# MCU.net
KiCad netlist of a schematic drawn in Altium Designer
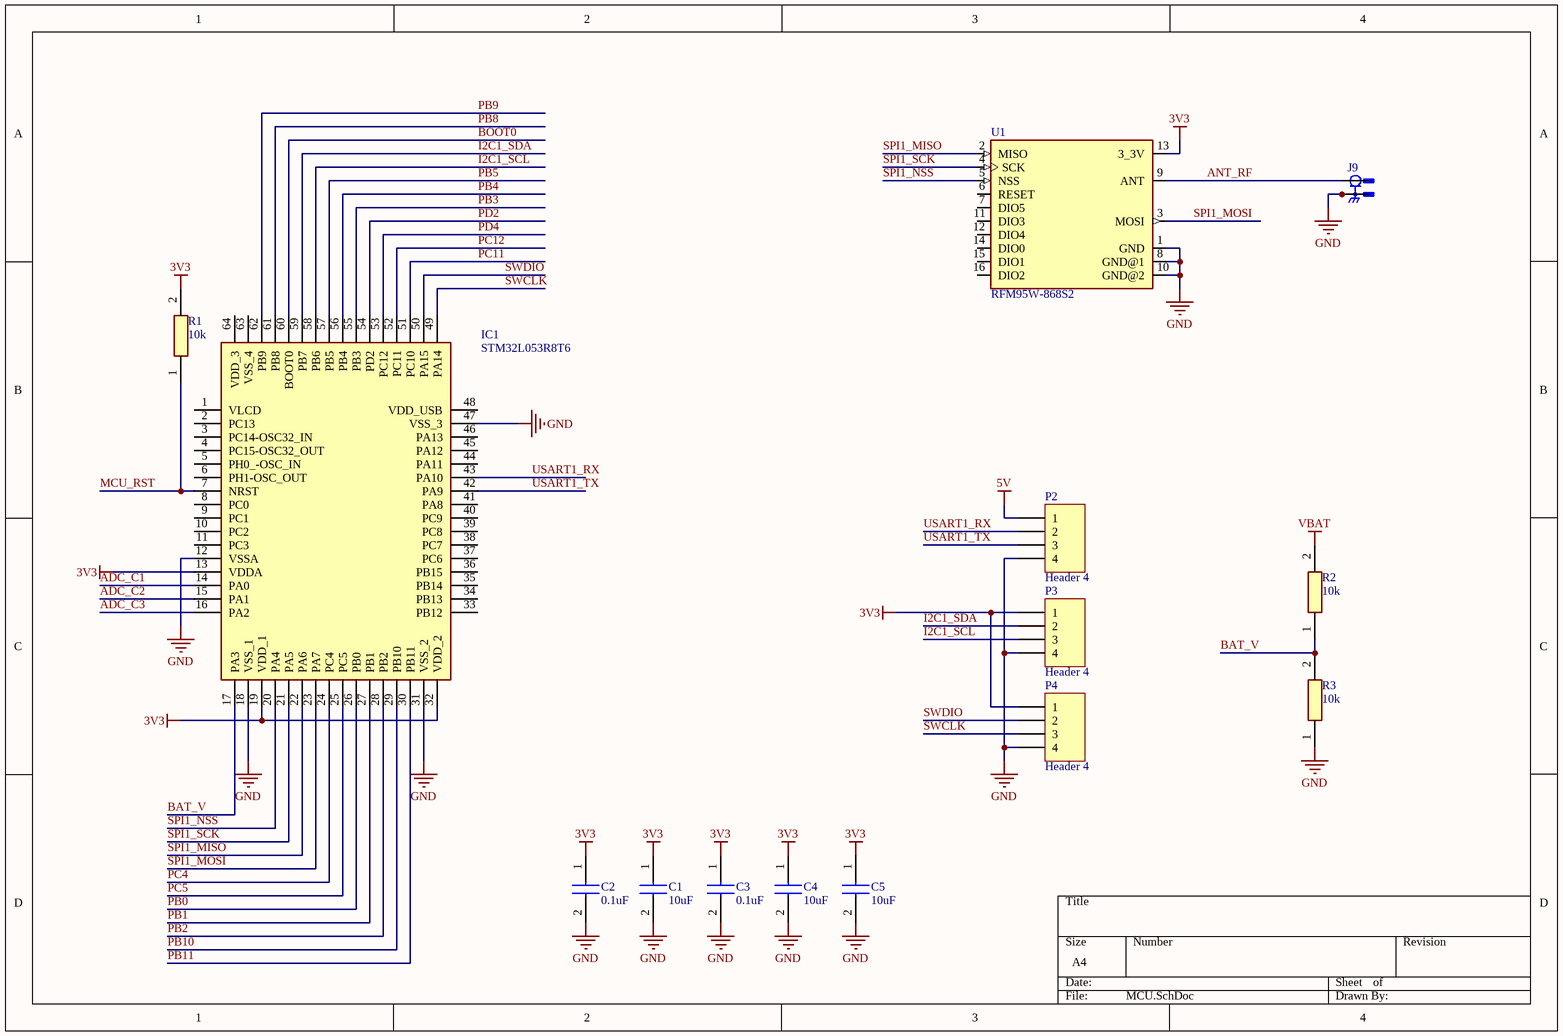
[diagram p0: MCU.SchDoc]

(export (version "E")
  (design (tool "Eeschema 10.0.6"))
  (components
    (comp (ref "C1")
      (value "10uF")
      (footprint "SamacSys:CAPC2012X94N")
      (description "Capacitor")
      (fields
        (field (name "MANUFACTURER_PART_NUMBER") "08055A130JAT2A")
        (field (name "MOUSER PART NUMBER") "581-08055A130JAT2A")
      )
      (libsource (lib "SamacSys") (part "08055A130JAT2A"))
    )
    (comp (ref "C2")
      (value "0.1uF")
      (footprint "SamacSys:CAPC2012X94N")
      (description "Capacitor")
      (fields
        (field (name "MANUFACTURER_PART_NUMBER") "08055A130JAT2A")
        (field (name "MOUSER PART NUMBER") "581-08055A130JAT2A")
      )
      (libsource (lib "SamacSys") (part "08055A130JAT2A"))
    )
    (comp (ref "C3")
      (value "0.1uF")
      (footprint "SamacSys:CAPC2012X94N")
      (description "Capacitor")
      (fields
        (field (name "MANUFACTURER_PART_NUMBER") "08055A130JAT2A")
        (field (name "MOUSER PART NUMBER") "581-08055A130JAT2A")
      )
      (libsource (lib "SamacSys") (part "08055A130JAT2A"))
    )
    (comp (ref "C4")
      (value "10uF")
      (footprint "SamacSys:CAPC2012X94N")
      (description "Capacitor")
      (fields
        (field (name "MANUFACTURER_PART_NUMBER") "08055A130JAT2A")
        (field (name "MOUSER PART NUMBER") "581-08055A130JAT2A")
      )
      (libsource (lib "SamacSys") (part "08055A130JAT2A"))
    )
    (comp (ref "C5")
      (value "10uF")
      (footprint "SamacSys:CAPC2012X94N")
      (description "Capacitor")
      (fields
        (field (name "MANUFACTURER_PART_NUMBER") "08055A130JAT2A")
        (field (name "MOUSER PART NUMBER") "581-08055A130JAT2A")
      )
      (libsource (lib "SamacSys") (part "08055A130JAT2A"))
    )
    (comp (ref "IC1")
      (value "STM32L053R8T6")
      (footprint "SamacSys:QFP50P1200X1200X160-64N")
      (description "Integrated Circuit")
      (fields (field (name "MOUSER PART NUMBER") "511-STM32L053R8T6"))
      (libsource (lib "*") (part "STM32L053R8T6"))
    )
    (comp (ref "J9")
      (value "CONSMA013.062-G")
      (footprint "LINX_CONSMA013.062-G")
      (description "SMA MALE EDGE MOUNT FOR 0.031\" THICK BOARD")
      (libsource (lib "CONSMA013.062-G") (part "CONSMA013.062-G"))
    )
    (comp (ref "P2")
      (value "Header 4")
      (footprint "HDR1X4")
      (description "Header, 4-Pin")
      (fields (field (name "PUBLISHER") "Altium Limited"))
      (libsource (lib "Miscellaneous Connectors") (part "Header 4"))
    )
    (comp (ref "P3")
      (value "Header 4")
      (footprint "HDR1X4")
      (description "Header, 4-Pin")
      (fields (field (name "PUBLISHER") "Altium Limited"))
      (libsource (lib "Miscellaneous Connectors") (part "Header 4"))
    )
    (comp (ref "P4")
      (value "Header 4")
      (footprint "HDR1X4")
      (description "Header, 4-Pin")
      (fields (field (name "PUBLISHER") "Altium Limited"))
      (libsource (lib "Miscellaneous Connectors") (part "Header 4"))
    )
    (comp (ref "R1")
      (value "10k")
      (footprint "SamacSys:RESC2012X65N")
      (description "Resistor")
      (fields (field (name "MANUFACTURER_PART_NUMBER") "CPF0805B102RE1"))
      (libsource (lib "SamacSys") (part "CPF0805B102RE1"))
    )
    (comp (ref "R2")
      (value "10k")
      (footprint "SamacSys:RESC2012X65N")
      (description "Resistor")
      (fields (field (name "MANUFACTURER_PART_NUMBER") "CPF0805B102RE1"))
      (libsource (lib "SamacSys") (part "CPF0805B102RE1"))
    )
    (comp (ref "R3")
      (value "10k")
      (footprint "SamacSys:RESC2012X65N")
      (description "Resistor")
      (fields (field (name "MANUFACTURER_PART_NUMBER") "CPF0805B102RE1"))
      (libsource (lib "SamacSys") (part "CPF0805B102RE1"))
    )
    (comp (ref "U1")
      (value "RFM95W-868S2")
      (footprint "XCVR_RFM95W-868S2")
      (description "Mod Txrx Lora +20dbm 868mhz Smd")
      (libsource (lib "RFM95W-868S2") (part "RFM95W-868S2"))
    )
  )
  (nets
    (net (code "1") (name "/ADC_C1") (class "Default")
      (node (ref "IC1") (pin "14") (pinfunction "PA0_14") (pintype "passive"))
    )
    (net (code "2") (name "/ADC_C2") (class "Default")
      (node (ref "IC1") (pin "15") (pinfunction "PA1_15") (pintype "passive"))
    )
    (net (code "3") (name "/ADC_C3") (class "Default")
      (node (ref "IC1") (pin "16") (pinfunction "PA2_16") (pintype "passive"))
    )
    (net (code "4") (name "/ANT_RF") (class "Default")
      (node (ref "J9") (pin "1") (pinfunction "1_1") (pintype "passive"))
      (node (ref "U1") (pin "9") (pinfunction "ANT_9") (pintype "passive"))
    )
    (net (code "5") (name "/BAT_V") (class "Default")
      (node (ref "IC1") (pin "17") (pinfunction "PA3_17") (pintype "passive"))
      (node (ref "R2") (pin "1") (pinfunction "1_1") (pintype "passive"))
      (node (ref "R3") (pin "2") (pinfunction "2_2") (pintype "passive"))
    )
    (net (code "6") (name "/BOOT0") (class "Default")
      (node (ref "IC1") (pin "60") (pinfunction "BOOT0_60") (pintype "passive"))
    )
    (net (code "7") (name "/I2C1_SCL") (class "Default")
      (node (ref "IC1") (pin "58") (pinfunction "PB6_58") (pintype "passive"))
      (node (ref "P3") (pin "3") (pinfunction "3_3") (pintype "passive"))
    )
    (net (code "8") (name "/I2C1_SDA") (class "Default")
      (node (ref "IC1") (pin "59") (pinfunction "PB7_59") (pintype "passive"))
      (node (ref "P3") (pin "2") (pinfunction "2_2") (pintype "passive"))
    )
    (net (code "9") (name "/MCU_RST") (class "Default")
      (node (ref "IC1") (pin "7") (pinfunction "NRST_7") (pintype "passive"))
      (node (ref "R1") (pin "1") (pinfunction "1_1") (pintype "passive"))
    )
    (net (code "10") (name "/PB0") (class "Default")
      (node (ref "IC1") (pin "26") (pinfunction "PB0_26") (pintype "passive"))
    )
    (net (code "11") (name "/PB1") (class "Default")
      (node (ref "IC1") (pin "27") (pinfunction "PB1_27") (pintype "passive"))
    )
    (net (code "12") (name "/PB2") (class "Default")
      (node (ref "IC1") (pin "28") (pinfunction "PB2_28") (pintype "passive"))
    )
    (net (code "13") (name "/PB3") (class "Default")
      (node (ref "IC1") (pin "55") (pinfunction "PB3_55") (pintype "passive"))
    )
    (net (code "14") (name "/PB4") (class "Default")
      (node (ref "IC1") (pin "56") (pinfunction "PB4_56") (pintype "passive"))
    )
    (net (code "15") (name "/PB5") (class "Default")
      (node (ref "IC1") (pin "57") (pinfunction "PB5_57") (pintype "passive"))
    )
    (net (code "16") (name "/PB8") (class "Default")
      (node (ref "IC1") (pin "61") (pinfunction "PB8_61") (pintype "passive"))
    )
    (net (code "17") (name "/PB9") (class "Default")
      (node (ref "IC1") (pin "62") (pinfunction "PB9_62") (pintype "passive"))
    )
    (net (code "18") (name "/PB10") (class "Default")
      (node (ref "IC1") (pin "29") (pinfunction "PB10_29") (pintype "passive"))
    )
    (net (code "19") (name "/PB11") (class "Default")
      (node (ref "IC1") (pin "30") (pinfunction "PB11_30") (pintype "passive"))
    )
    (net (code "20") (name "/PC4") (class "Default")
      (node (ref "IC1") (pin "24") (pinfunction "PC4_24") (pintype "passive"))
    )
    (net (code "21") (name "/PC5") (class "Default")
      (node (ref "IC1") (pin "25") (pinfunction "PC5_25") (pintype "passive"))
    )
    (net (code "22") (name "/PC11") (class "Default")
      (node (ref "IC1") (pin "51") (pinfunction "PC10_51") (pintype "passive"))
    )
    (net (code "23") (name "/PC12") (class "Default")
      (node (ref "IC1") (pin "52") (pinfunction "PC11_52") (pintype "passive"))
    )
    (net (code "24") (name "/PD2") (class "Default")
      (node (ref "IC1") (pin "54") (pinfunction "PD2_54") (pintype "passive"))
    )
    (net (code "25") (name "/PD4") (class "Default")
      (node (ref "IC1") (pin "53") (pinfunction "PC12_53") (pintype "passive"))
    )
    (net (code "26") (name "/SPI1_MISO") (class "Default")
      (node (ref "IC1") (pin "22") (pinfunction "PA6_22") (pintype "passive"))
      (node (ref "U1") (pin "2") (pinfunction "MISO_2") (pintype "input"))
    )
    (net (code "27") (name "/SPI1_MOSI") (class "Default")
      (node (ref "IC1") (pin "23") (pinfunction "PA7_23") (pintype "passive"))
      (node (ref "U1") (pin "3") (pinfunction "MOSI_3") (pintype "output"))
    )
    (net (code "28") (name "/SPI1_NSS") (class "Default")
      (node (ref "IC1") (pin "20") (pinfunction "PA4_20") (pintype "passive"))
      (node (ref "U1") (pin "5") (pinfunction "NSS_5") (pintype "input"))
    )
    (net (code "29") (name "/SPI1_SCK") (class "Default")
      (node (ref "IC1") (pin "21") (pinfunction "PA5_21") (pintype "passive"))
      (node (ref "U1") (pin "4") (pinfunction "SCK_4") (pintype "input"))
    )
    (net (code "30") (name "/SWCLK") (class "Default")
      (node (ref "IC1") (pin "49") (pinfunction "PA14_49") (pintype "passive"))
      (node (ref "P4") (pin "3") (pinfunction "3_3") (pintype "passive"))
    )
    (net (code "31") (name "/SWDIO") (class "Default")
      (node (ref "IC1") (pin "50") (pinfunction "PA15_50") (pintype "passive"))
      (node (ref "P4") (pin "2") (pinfunction "2_2") (pintype "passive"))
    )
    (net (code "32") (name "/USART1_RX") (class "Default")
      (node (ref "IC1") (pin "43") (pinfunction "PA10_43") (pintype "passive"))
      (node (ref "P2") (pin "2") (pinfunction "2_2") (pintype "passive"))
    )
    (net (code "33") (name "/USART1_TX") (class "Default")
      (node (ref "IC1") (pin "42") (pinfunction "PA9_42") (pintype "passive"))
      (node (ref "P2") (pin "3") (pinfunction "3_3") (pintype "passive"))
    )
    (net (code "34") (name "3V3") (class "Default")
      (node (ref "C1") (pin "1") (pinfunction "1_1") (pintype "passive"))
      (node (ref "C2") (pin "1") (pinfunction "1_1") (pintype "passive"))
      (node (ref "C3") (pin "1") (pinfunction "1_1") (pintype "passive"))
      (node (ref "C4") (pin "1") (pinfunction "1_1") (pintype "passive"))
      (node (ref "C5") (pin "1") (pinfunction "1_1") (pintype "passive"))
      (node (ref "IC1") (pin "13") (pinfunction "VDDA_13") (pintype "passive"))
      (node (ref "IC1") (pin "19") (pinfunction "VDD_1_19") (pintype "passive"))
      (node (ref "IC1") (pin "32") (pinfunction "VDD_2_32") (pintype "passive"))
      (node (ref "P3") (pin "1") (pinfunction "1_1") (pintype "passive"))
      (node (ref "P4") (pin "1") (pinfunction "1_1") (pintype "passive"))
      (node (ref "R1") (pin "2") (pinfunction "2_2") (pintype "passive"))
      (node (ref "U1") (pin "13") (pinfunction "3_3V_13") (pintype "power_in"))
    )
    (net (code "35") (name "5V") (class "Default")
      (node (ref "P2") (pin "1") (pinfunction "1_1") (pintype "passive"))
    )
    (net (code "36") (name "GND") (class "Default")
      (node (ref "C1") (pin "2") (pinfunction "2_2") (pintype "passive"))
      (node (ref "C2") (pin "2") (pinfunction "2_2") (pintype "passive"))
      (node (ref "C3") (pin "2") (pinfunction "2_2") (pintype "passive"))
      (node (ref "C4") (pin "2") (pinfunction "2_2") (pintype "passive"))
      (node (ref "C5") (pin "2") (pinfunction "2_2") (pintype "passive"))
      (node (ref "IC1") (pin "12") (pinfunction "VSSA_12") (pintype "passive"))
      (node (ref "IC1") (pin "18") (pinfunction "VSS_1_18") (pintype "passive"))
      (node (ref "IC1") (pin "31") (pinfunction "VSS_2_31") (pintype "passive"))
      (node (ref "IC1") (pin "47") (pinfunction "VSS_3_47") (pintype "passive"))
      (node (ref "J9") (pin "S1") (pinfunction "2_S1") (pintype "passive"))
      (node (ref "J9") (pin "S2") (pinfunction "2_S2") (pintype "passive"))
      (node (ref "J9") (pin "S3") (pinfunction "2_S3") (pintype "passive"))
      (node (ref "J9") (pin "S4") (pinfunction "2_S4") (pintype "passive"))
      (node (ref "P2") (pin "4") (pinfunction "4_4") (pintype "passive"))
      (node (ref "P3") (pin "4") (pinfunction "4_4") (pintype "passive"))
      (node (ref "P4") (pin "4") (pinfunction "4_4") (pintype "passive"))
      (node (ref "R3") (pin "1") (pinfunction "1_1") (pintype "passive"))
      (node (ref "U1") (pin "1") (pinfunction "GND_1") (pintype "power_in"))
      (node (ref "U1") (pin "10") (pinfunction "GND@2_10") (pintype "power_in"))
      (node (ref "U1") (pin "8") (pinfunction "GND@1_8") (pintype "power_in"))
    )
    (net (code "37") (name "VBAT") (class "Default")
      (node (ref "R2") (pin "2") (pinfunction "2_2") (pintype "passive"))
    )
    (net (code "38") (name "unconnected-(IC1-PA8-Pad41)") (class "Default")
      (node (ref "IC1") (pin "41") (pinfunction "PA8_41") (pintype "passive"))
    )
    (net (code "39") (name "unconnected-(IC1-PA11-Pad44)") (class "Default")
      (node (ref "IC1") (pin "44") (pinfunction "PA11_44") (pintype "passive"))
    )
    (net (code "40") (name "unconnected-(IC1-PA12-Pad45)") (class "Default")
      (node (ref "IC1") (pin "45") (pinfunction "PA12_45") (pintype "passive"))
    )
    (net (code "41") (name "unconnected-(IC1-PA13-Pad46)") (class "Default")
      (node (ref "IC1") (pin "46") (pinfunction "PA13_46") (pintype "passive"))
    )
    (net (code "42") (name "unconnected-(IC1-PB12-Pad33)") (class "Default")
      (node (ref "IC1") (pin "33") (pinfunction "PB12_33") (pintype "passive"))
    )
    (net (code "43") (name "unconnected-(IC1-PB13-Pad34)") (class "Default")
      (node (ref "IC1") (pin "34") (pinfunction "PB13_34") (pintype "passive"))
    )
    (net (code "44") (name "unconnected-(IC1-PB14-Pad35)") (class "Default")
      (node (ref "IC1") (pin "35") (pinfunction "PB14_35") (pintype "passive"))
    )
    (net (code "45") (name "unconnected-(IC1-PB15-Pad36)") (class "Default")
      (node (ref "IC1") (pin "36") (pinfunction "PB15_36") (pintype "passive"))
    )
    (net (code "46") (name "unconnected-(IC1-PC0-Pad8)") (class "Default")
      (node (ref "IC1") (pin "8") (pinfunction "PC0_8") (pintype "passive"))
    )
    (net (code "47") (name "unconnected-(IC1-PC1-Pad9)") (class "Default")
      (node (ref "IC1") (pin "9") (pinfunction "PC1_9") (pintype "passive"))
    )
    (net (code "48") (name "unconnected-(IC1-PC2-Pad10)") (class "Default")
      (node (ref "IC1") (pin "10") (pinfunction "PC2_10") (pintype "passive"))
    )
    (net (code "49") (name "unconnected-(IC1-PC3-Pad11)") (class "Default")
      (node (ref "IC1") (pin "11") (pinfunction "PC3_11") (pintype "passive"))
    )
    (net (code "50") (name "unconnected-(IC1-PC6-Pad37)") (class "Default")
      (node (ref "IC1") (pin "37") (pinfunction "PC6_37") (pintype "passive"))
    )
    (net (code "51") (name "unconnected-(IC1-PC7-Pad38)") (class "Default")
      (node (ref "IC1") (pin "38") (pinfunction "PC7_38") (pintype "passive"))
    )
    (net (code "52") (name "unconnected-(IC1-PC8-Pad39)") (class "Default")
      (node (ref "IC1") (pin "39") (pinfunction "PC8_39") (pintype "passive"))
    )
    (net (code "53") (name "unconnected-(IC1-PC9-Pad40)") (class "Default")
      (node (ref "IC1") (pin "40") (pinfunction "PC9_40") (pintype "passive"))
    )
    (net (code "54") (name "unconnected-(IC1-PC13-Pad2)") (class "Default")
      (node (ref "IC1") (pin "2") (pinfunction "PC13_2") (pintype "passive"))
    )
    (net (code "55") (name "unconnected-(IC1-PC14-OSC32_IN-Pad3)") (class "Default")
      (node (ref "IC1") (pin "3") (pinfunction "PC14-OSC32_IN_3") (pintype "passive"))
    )
    (net (code "56") (name "unconnected-(IC1-PC15-OSC32_OUT-Pad4)") (class "Default")
      (node (ref "IC1") (pin "4") (pinfunction "PC15-OSC32_OUT_4") (pintype "passive"))
    )
    (net (code "57") (name "unconnected-(IC1-PH0_-OSC_IN-Pad5)") (class "Default")
      (node (ref "IC1") (pin "5") (pinfunction "PH0_-OSC_IN_5") (pintype "passive"))
    )
    (net (code "58") (name "unconnected-(IC1-PH1-OSC_OUT-Pad6)") (class "Default")
      (node (ref "IC1") (pin "6") (pinfunction "PH1-OSC_OUT_6") (pintype "passive"))
    )
    (net (code "59") (name "unconnected-(IC1-VDD_3-Pad64)") (class "Default")
      (node (ref "IC1") (pin "64") (pinfunction "VDD_3_64") (pintype "passive"))
    )
    (net (code "60") (name "unconnected-(IC1-VDD_USB-Pad48)") (class "Default")
      (node (ref "IC1") (pin "48") (pinfunction "VDD_USB_48") (pintype "passive"))
    )
    (net (code "61") (name "unconnected-(IC1-VLCD-Pad1)") (class "Default")
      (node (ref "IC1") (pin "1") (pinfunction "VLCD_1") (pintype "passive"))
    )
    (net (code "62") (name "unconnected-(IC1-VSS_4-Pad63)") (class "Default")
      (node (ref "IC1") (pin "63") (pinfunction "VSS_4_63") (pintype "passive"))
    )
    (net (code "63") (name "unconnected-(U1-DIO0-Pad14)") (class "Default")
      (node (ref "U1") (pin "14") (pinfunction "DIO0_14") (pintype "bidirectional"))
    )
    (net (code "64") (name "unconnected-(U1-DIO1-Pad15)") (class "Default")
      (node (ref "U1") (pin "15") (pinfunction "DIO1_15") (pintype "bidirectional"))
    )
    (net (code "65") (name "unconnected-(U1-DIO2-Pad16)") (class "Default")
      (node (ref "U1") (pin "16") (pinfunction "DIO2_16") (pintype "bidirectional"))
    )
    (net (code "66") (name "unconnected-(U1-DIO3-Pad11)") (class "Default")
      (node (ref "U1") (pin "11") (pinfunction "DIO3_11") (pintype "bidirectional"))
    )
    (net (code "67") (name "unconnected-(U1-DIO4-Pad12)") (class "Default")
      (node (ref "U1") (pin "12") (pinfunction "DIO4_12") (pintype "bidirectional"))
    )
    (net (code "68") (name "unconnected-(U1-DIO5-Pad7)") (class "Default")
      (node (ref "U1") (pin "7") (pinfunction "DIO5_7") (pintype "bidirectional"))
    )
    (net (code "69") (name "unconnected-(U1-RESET-Pad6)") (class "Default")
      (node (ref "U1") (pin "6") (pinfunction "RESET_6") (pintype "bidirectional"))
    )
  )
)
